# RF_Data.net
KiCad netlist of a schematic drawn in Altium Designer
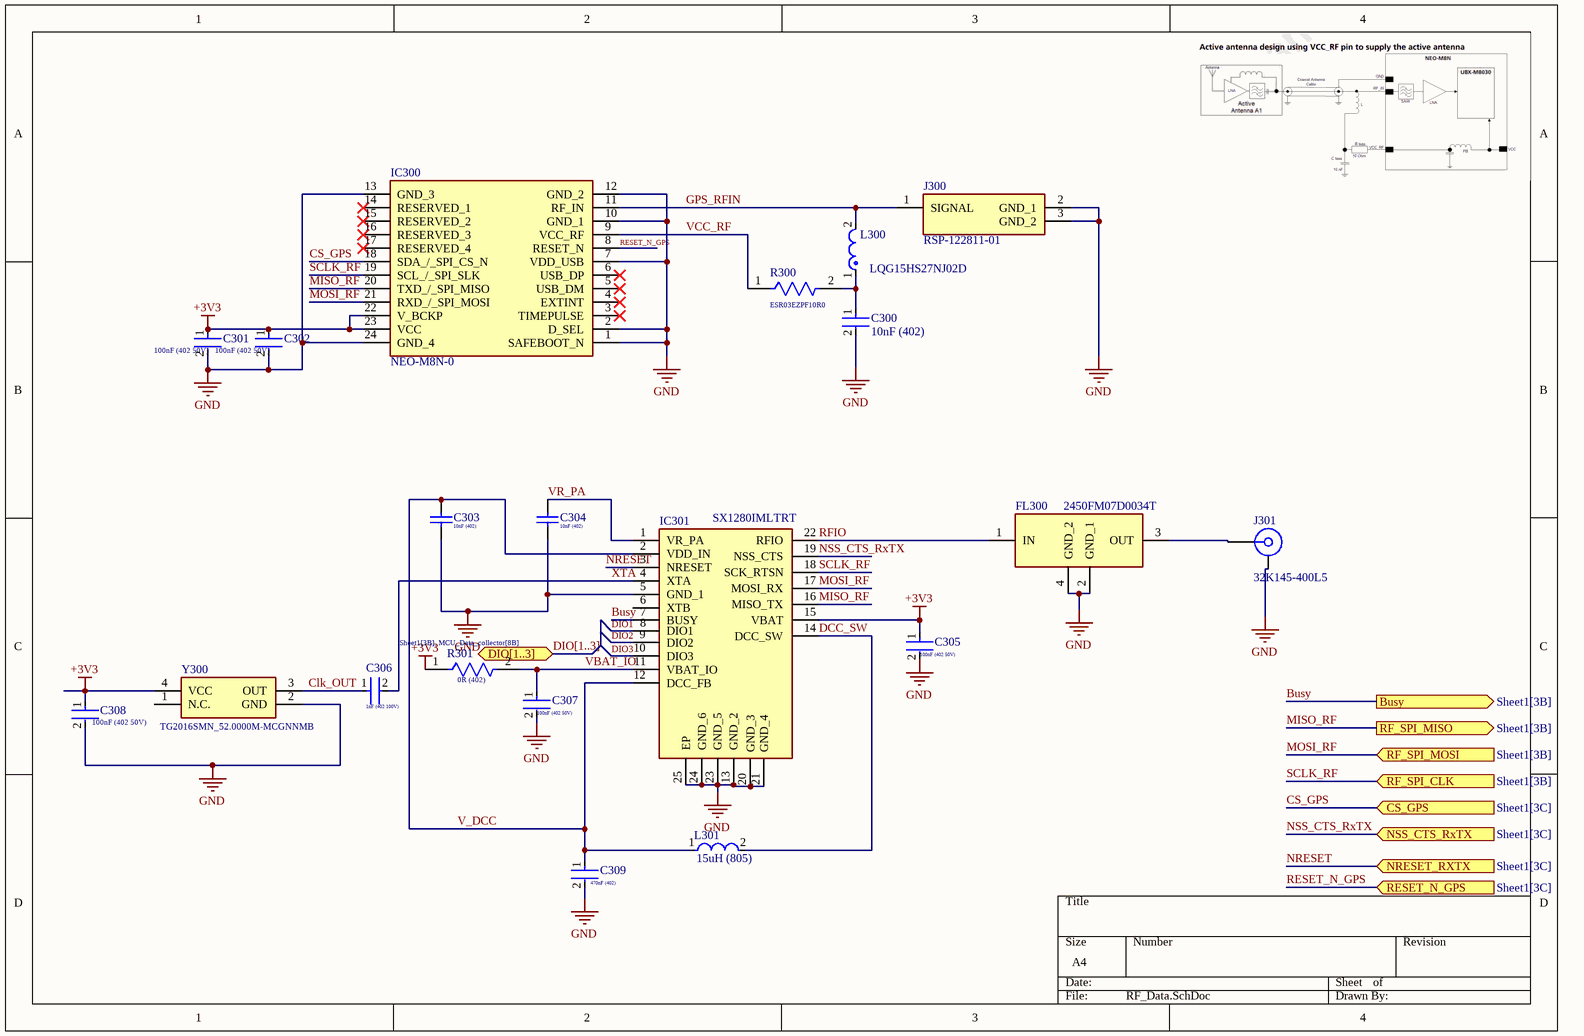
[diagram p0: RF_Data.SchDoc]

(export (version "E")
  (design (tool "Eeschema 10.0.6"))
  (components
    (comp (ref "C300")
      (value "10nF (402)")
      (footprint "FP-CL165-IPC_C")
      (description "Cap Ceramic 10nF 50V X7R ±10% SMD 0402 +125°C Paper T/R")
      (fields (field (name "VOLTAGE") "50V") (field (name "TOLERANCE") "10%"))
      (libsource (lib "Altium Content Vault") (part "b4654b650e69147ec39a6b967a45e02"))
    )
    (comp (ref "C301")
      (value "100nF (402 50V)")
      (footprint "FP-CL779-IPC_C")
      (description "Cap Ceramic 100nF 50V X7R ±10% SMD 0402 +125°C Paper T/R")
      (libsource (lib "Altium Content Vault") (part "b4654b650e69147ec39a6b967a45e02"))
    )
    (comp (ref "C302")
      (value "100nF (402 50V)")
      (footprint "FP-CL779-IPC_C")
      (description "Cap Ceramic 100nF 50V X7R ±10% SMD 0402 +125°C Paper T/R")
      (libsource (lib "Altium Content Vault") (part "b4654b650e69147ec39a6b967a45e02"))
    )
    (comp (ref "C303")
      (value "10nF (402)")
      (footprint "CAPC1005X55X25LL05T10")
      (fields (field (name "MANUFACTURER") "Murata") (field (name "PART NUMBER") "GRM155R71E103KA01D"))
      (libsource (lib "Altium Content Vault") (part "CAP"))
    )
    (comp (ref "C304")
      (value "10nF (402)")
      (footprint "CAPC1005X55X25LL05T10")
      (fields (field (name "MANUFACTURER") "Murata") (field (name "PART NUMBER") "GRM155R71E103KA01D"))
      (libsource (lib "Altium Content Vault") (part "CAP"))
    )
    (comp (ref "C305")
      (value "100nF (402 50V)")
      (footprint "FP-CL779-IPC_C")
      (description "Cap Ceramic 100nF 50V X7R ±10% SMD 0402 +125°C Paper T/R")
      (libsource (lib "Altium Content Vault") (part "b4654b650e69147ec39a6b967a45e02"))
    )
    (comp (ref "C306")
      (value "1nF (402 100V)")
      (footprint "FP-GCM155-0_05-MFG")
      (description "Ceramic Capacitor for Automotive 1nF ±10% 100VDC X7R 0402 Paper T/R")
      (fields (field (name "VOLTAGE") "100V") (field (name "TOLERANCE") "10%"))
      (libsource (lib "Altium Content Vault") (part "02cd4be3c70576c341d710602a673aa"))
    )
    (comp (ref "C307")
      (value "100nF (402 50V)")
      (footprint "FP-CL779-IPC_C")
      (description "Cap Ceramic 100nF 50V X7R ±10% SMD 0402 +125°C Paper T/R")
      (libsource (lib "Altium Content Vault") (part "b4654b650e69147ec39a6b967a45e02"))
    )
    (comp (ref "C308")
      (value "100nF (402 50V)")
      (footprint "FP-CL779-IPC_C")
      (description "Cap Ceramic 100nF 50V X7R ±10% SMD 0402 +125°C Paper T/R")
      (libsource (lib "Altium Content Vault") (part "b4654b650e69147ec39a6b967a45e02"))
    )
    (comp (ref "C309")
      (value "470nF (402)")
      (footprint "FP-GRM15-0_1-MFG")
      (description "CAP CER 0.47UF 10V X5R 0402")
      (fields
        (field (name "MANUFACTURER") "Murata Electronics North America")
        (field (name "MANUFACTURER PART NUMBER") "GRM155R61A474KE15D")
      )
      (libsource (lib "Altium Content Vault") (part "11868f565c42a9108669ba33697ecf6"))
    )
    (comp (ref "FL300")
      (value "2450FM07D0034T")
      (footprint "SamacSys:2450FM07D0034T")
      (description "Filter")
      (fields (field (name "MOUSER PART NUMBER") "609-2450FM07D0034T"))
      (libsource (lib "SamacSys") (part "2450FM07D0034T"))
    )
    (comp (ref "IC300")
      (value "NEO-M8N-0")
      (footprint "SamacSys:NEO-M8T")
      (description "Integrated Circuit")
      (fields (field (name "MOUSER PART NUMBER") "377-NEO-M8N-0"))
      (libsource (lib "*") (part "NEO-M8N-0"))
    )
    (comp (ref "IC301")
      (value "SX1280IMLTRT")
      (footprint "SamacSys:QFN50P400X400X100-25N-D")
      (description "Integrated Circuit")
      (fields (field (name "MOUSER PART NUMBER") "947-SX1280IMLTRT"))
      (libsource (lib "SamacSys") (part "SX1280IMLTRT"))
    )
    (comp (ref "J300")
      (value "RSP-122811-01")
      (footprint "SamacSys:RSP12281101")
      (description "Connector")
      (fields (field (name "MOUSER PART NUMBER") "200-RSP-122811-01"))
      (libsource (lib "*") (part "RSP-122811-01"))
    )
    (comp (ref "J301")
      (value "32K145-400L5")
      (footprint "ROS-32K145-400L5_V")
      (description "SMA Right Angle Jack, Edge Mount, Up to 18 GHz, -55 to 155 degC")
      (fields (field (name "MANUFACTURER") "Rosenberger"))
      (libsource (lib "Altium Content Vault") (part "ROS-CN-1F-RF1-A"))
    )
    (comp (ref "L300")
      (value "LQG15HS27NJ02D")
      (footprint "FP-LQG15HH_02-IPC_C")
      (description "Multilayer type RF Inductor 27nH ±5% 0.46Ω 350mA 0402")
      (fields (field (name "TOLERANCE") "5%"))
      (libsource (lib "Altium Content Vault") (part "4cc4b267dca4c8e51f7102f422741d8"))
    )
    (comp (ref "L301")
      (value "15uH (805)")
      (footprint "FP-MLZ2012-1_25-IPC_C")
      (description "Shielded Multilayer Inductor 15uH ±20% 250mA 1235mΩ SMD 0805")
      (fields (field (name "TOLERANCE") "20%"))
      (libsource (lib "Altium Content Vault") (part "725321dda6339637d4d059423bc1c3c"))
    )
    (comp (ref "R300")
      (value "ESR03EZPF10R0")
      (footprint "FP-ESR03-IPC_B")
      (description "RES SMD 10 OHM 1% 1/4W 0603")
      (fields (field (name "TOLERANCE") "1%"))
      (libsource (lib "Altium Content Vault") (part "1029c3af85768c4190bb7ad29bc67b5"))
    )
    (comp (ref "R301")
      (value "0R (402)")
      (footprint "FP-CRCW0402-e3-IPC_C")
      (description "RES Thick Film, 0Ω, 0.063W, 0402")
      (fields (field (name "TOLERANCE") "5%"))
      (libsource (lib "Altium Content Vault") (part "1029c3af85768c4190bb7ad29bc67b5"))
    )
    (comp (ref "Y300")
      (value "TG2016SMN_52.0000M-MCGNNMB")
      (footprint "SamacSys:TG2016SMN520000MMCGNNMB")
      (description "Crystal or Oscillator")
      (fields (field (name "MANUFACTURER_PART_NUMBER") "TG2016SMN 52.0000M-MCGNNMB"))
      (libsource (lib "*") (part "TG2016SMN_52.0000M-MCGNNMB"))
    )
  )
  (nets
    (net (code "1") (name "+3V3") (class "Default")
      (node (ref "C301") (pin "1") (pinfunction "1_1") (pintype "passive"))
      (node (ref "C302") (pin "1") (pinfunction "1_1") (pintype "passive"))
      (node (ref "C305") (pin "1") (pinfunction "1_1") (pintype "passive"))
      (node (ref "C308") (pin "1") (pinfunction "1_1") (pintype "passive"))
      (node (ref "IC300") (pin "22") (pinfunction "V_BCKP_22") (pintype "passive"))
      (node (ref "IC300") (pin "23") (pinfunction "VCC_23") (pintype "passive"))
      (node (ref "IC301") (pin "15") (pinfunction "VBAT_15") (pintype "passive"))
      (node (ref "R301") (pin "1") (pinfunction "1_1") (pintype "passive"))
      (node (ref "Y300") (pin "4") (pinfunction "VCC_4") (pintype "passive"))
    )
    (net (code "2") (name "/Busy") (class "Default")
      (node (ref "IC301") (pin "7") (pinfunction "BUSY_7") (pintype "passive"))
    )
    (net (code "3") (name "/CS_GPS") (class "Default")
      (node (ref "IC300") (pin "18") (pinfunction "SDA_/_SPI_CS_N_18") (pintype "passive"))
    )
    (net (code "4") (name "/Clk_OUT") (class "Default")
      (node (ref "C306") (pin "1") (pinfunction "1_1") (pintype "passive"))
      (node (ref "Y300") (pin "3") (pinfunction "OUT_3") (pintype "passive"))
    )
    (net (code "5") (name "/DCC_SW") (class "Default")
      (node (ref "IC301") (pin "14") (pinfunction "DCC_SW_14") (pintype "passive"))
      (node (ref "L301") (pin "2") (pinfunction "2_2") (pintype "passive"))
    )
    (net (code "6") (name "/DIO1") (class "Default")
      (node (ref "IC301") (pin "8") (pinfunction "DIO1_8") (pintype "passive"))
    )
    (net (code "7") (name "/DIO2") (class "Default")
      (node (ref "IC301") (pin "9") (pinfunction "DIO2_9") (pintype "passive"))
    )
    (net (code "8") (name "/DIO3") (class "Default")
      (node (ref "IC301") (pin "10") (pinfunction "DIO3_10") (pintype "passive"))
    )
    (net (code "10") (name "/GPS_RFIN") (class "Default")
      (node (ref "IC300") (pin "11") (pinfunction "RF_IN_11") (pintype "passive"))
      (node (ref "J300") (pin "1") (pinfunction "SIGNAL_1") (pintype "passive"))
      (node (ref "L300") (pin "2") (pinfunction "2_2") (pintype "passive"))
    )
    (net (code "11") (name "/MISO_RF") (class "Default")
      (node (ref "IC300") (pin "20") (pinfunction "TXD_/_SPI_MISO_20") (pintype "passive"))
      (node (ref "IC301") (pin "16") (pinfunction "MISO_TX_16") (pintype "passive"))
    )
    (net (code "12") (name "/MOSI_RF") (class "Default")
      (node (ref "IC300") (pin "21") (pinfunction "RXD_/_SPI_MOSI_21") (pintype "passive"))
      (node (ref "IC301") (pin "17") (pinfunction "MOSI_RX_17") (pintype "passive"))
    )
    (net (code "13") (name "/NRESET") (class "Default")
      (node (ref "IC301") (pin "3") (pinfunction "NRESET_3") (pintype "passive"))
    )
    (net (code "14") (name "/NSS_CTS_RxTX") (class "Default")
      (node (ref "IC301") (pin "19") (pinfunction "NSS_CTS_19") (pintype "passive"))
    )
    (net (code "15") (name "/RESET_N_GPS") (class "Default")
      (node (ref "IC300") (pin "8") (pinfunction "RESET_N_8") (pintype "passive"))
    )
    (net (code "16") (name "/RFIO") (class "Default")
      (node (ref "FL300") (pin "1") (pinfunction "IN_1") (pintype "passive"))
      (node (ref "IC301") (pin "22") (pinfunction "RFIO_22") (pintype "passive"))
    )
    (net (code "17") (name "/SCLK_RF") (class "Default")
      (node (ref "IC300") (pin "19") (pinfunction "SCL_/_SPI_SLK_19") (pintype "passive"))
      (node (ref "IC301") (pin "18") (pinfunction "SCK_RTSN_18") (pintype "passive"))
    )
    (net (code "18") (name "/VBAT_IO") (class "Default")
      (node (ref "C307") (pin "1") (pinfunction "1_1") (pintype "passive"))
      (node (ref "IC301") (pin "11") (pinfunction "VBAT_IO_11") (pintype "passive"))
      (node (ref "R301") (pin "2") (pinfunction "2_2") (pintype "passive"))
    )
    (net (code "19") (name "/VCC_RF") (class "Default")
      (node (ref "IC300") (pin "9") (pinfunction "VCC_RF_9") (pintype "passive"))
      (node (ref "R300") (pin "1") (pinfunction "1_1") (pintype "passive"))
    )
    (net (code "20") (name "/VR_PA") (class "Default")
      (node (ref "C304") (pin "2") (pinfunction "2_2") (pintype "passive"))
      (node (ref "IC301") (pin "1") (pinfunction "VR_PA_1") (pintype "passive"))
    )
    (net (code "21") (name "/V_DCC") (class "Default")
      (node (ref "C303") (pin "2") (pinfunction "2_2") (pintype "passive"))
      (node (ref "C309") (pin "1") (pinfunction "1_1") (pintype "passive"))
      (node (ref "IC301") (pin "12") (pinfunction "DCC_FB_12") (pintype "passive"))
      (node (ref "IC301") (pin "2") (pinfunction "VDD_IN_2") (pintype "passive"))
      (node (ref "L301") (pin "1") (pinfunction "1_1") (pintype "passive"))
    )
    (net (code "22") (name "/XTA") (class "Default")
      (node (ref "C306") (pin "2") (pinfunction "2_2") (pintype "passive"))
      (node (ref "IC301") (pin "4") (pinfunction "XTA_4") (pintype "passive"))
    )
    (net (code "23") (name "GND") (class "Default")
      (node (ref "C300") (pin "2") (pinfunction "2_2") (pintype "passive"))
      (node (ref "C301") (pin "2") (pinfunction "2_2") (pintype "passive"))
      (node (ref "C302") (pin "2") (pinfunction "2_2") (pintype "passive"))
      (node (ref "C303") (pin "1") (pinfunction "1_1") (pintype "passive"))
      (node (ref "C304") (pin "1") (pinfunction "1_1") (pintype "passive"))
      (node (ref "C305") (pin "2") (pinfunction "2_2") (pintype "passive"))
      (node (ref "C307") (pin "2") (pinfunction "2_2") (pintype "passive"))
      (node (ref "C308") (pin "2") (pinfunction "2_2") (pintype "passive"))
      (node (ref "C309") (pin "2") (pinfunction "2_2") (pintype "passive"))
      (node (ref "FL300") (pin "2") (pinfunction "GND_1_2") (pintype "passive"))
      (node (ref "FL300") (pin "4") (pinfunction "GND_2_4") (pintype "passive"))
      (node (ref "IC300") (pin "1") (pinfunction "SAFEBOOT_N_1") (pintype "passive"))
      (node (ref "IC300") (pin "10") (pinfunction "GND_1_10") (pintype "passive"))
      (node (ref "IC300") (pin "12") (pinfunction "GND_2_12") (pintype "passive"))
      (node (ref "IC300") (pin "13") (pinfunction "GND_3_13") (pintype "passive"))
      (node (ref "IC300") (pin "2") (pinfunction "D_SEL_2") (pintype "passive"))
      (node (ref "IC300") (pin "24") (pinfunction "GND_4_24") (pintype "passive"))
      (node (ref "IC300") (pin "7") (pinfunction "VDD_USB_7") (pintype "passive"))
      (node (ref "IC301") (pin "13") (pinfunction "GND_2_13") (pintype "passive"))
      (node (ref "IC301") (pin "20") (pinfunction "GND_3_20") (pintype "passive"))
      (node (ref "IC301") (pin "21") (pinfunction "GND_4_21") (pintype "passive"))
      (node (ref "IC301") (pin "23") (pinfunction "GND_5_23") (pintype "passive"))
      (node (ref "IC301") (pin "24") (pinfunction "GND_6_24") (pintype "passive"))
      (node (ref "IC301") (pin "25") (pinfunction "EP_25") (pintype "passive"))
      (node (ref "IC301") (pin "5") (pinfunction "GND_1_5") (pintype "passive"))
      (node (ref "J300") (pin "2") (pinfunction "GND_1_2") (pintype "passive"))
      (node (ref "J300") (pin "3") (pinfunction "GND_2_3") (pintype "passive"))
      (node (ref "J301") (pin "MP") (pinfunction "MP_MP") (pintype "passive"))
      (node (ref "Y300") (pin "2") (pinfunction "GND_2") (pintype "passive"))
    )
    (net (code "24") (name "Net-(C300-Pad1)") (class "Default")
      (node (ref "C300") (pin "1") (pinfunction "1_1") (pintype "passive"))
      (node (ref "L300") (pin "1") (pinfunction "1_1") (pintype "passive"))
      (node (ref "R300") (pin "2") (pinfunction "2_2") (pintype "passive"))
    )
    (net (code "25") (name "Net-(FL300-OUT)") (class "Default")
      (node (ref "FL300") (pin "3") (pinfunction "OUT_3") (pintype "passive"))
      (node (ref "J301") (pin "1") (pinfunction "1_1") (pintype "passive"))
    )
    (net (code "26") (name "unconnected-(IC300-EXTINT-Pad4)") (class "Default")
      (node (ref "IC300") (pin "4") (pinfunction "EXTINT_4") (pintype "passive+no_connect"))
    )
    (net (code "27") (name "unconnected-(IC300-RESERVED_1-Pad14)") (class "Default")
      (node (ref "IC300") (pin "14") (pinfunction "RESERVED_1_14") (pintype "passive+no_connect"))
    )
    (net (code "28") (name "unconnected-(IC300-RESERVED_2-Pad15)") (class "Default")
      (node (ref "IC300") (pin "15") (pinfunction "RESERVED_2_15") (pintype "passive+no_connect"))
    )
    (net (code "29") (name "unconnected-(IC300-RESERVED_3-Pad16)") (class "Default")
      (node (ref "IC300") (pin "16") (pinfunction "RESERVED_3_16") (pintype "passive+no_connect"))
    )
    (net (code "30") (name "unconnected-(IC300-RESERVED_4-Pad17)") (class "Default")
      (node (ref "IC300") (pin "17") (pinfunction "RESERVED_4_17") (pintype "passive+no_connect"))
    )
    (net (code "31") (name "unconnected-(IC300-TIMEPULSE-Pad3)") (class "Default")
      (node (ref "IC300") (pin "3") (pinfunction "TIMEPULSE_3") (pintype "passive+no_connect"))
    )
    (net (code "32") (name "unconnected-(IC300-USB_DM-Pad5)") (class "Default")
      (node (ref "IC300") (pin "5") (pinfunction "USB_DM_5") (pintype "passive+no_connect"))
    )
    (net (code "33") (name "unconnected-(IC300-USB_DP-Pad6)") (class "Default")
      (node (ref "IC300") (pin "6") (pinfunction "USB_DP_6") (pintype "passive+no_connect"))
    )
    (net (code "34") (name "unconnected-(IC301-XTB-Pad6)") (class "Default")
      (node (ref "IC301") (pin "6") (pinfunction "XTB_6") (pintype "passive"))
    )
    (net (code "35") (name "unconnected-(Y300-N.C.-Pad1)") (class "Default")
      (node (ref "Y300") (pin "1") (pinfunction "N.C._1") (pintype "passive"))
    )
  )
)
